# SCH_vibrating-mamba-snake_2024-07-07_1.net
KiCad netlist of a schematic drawn in EasyEDA
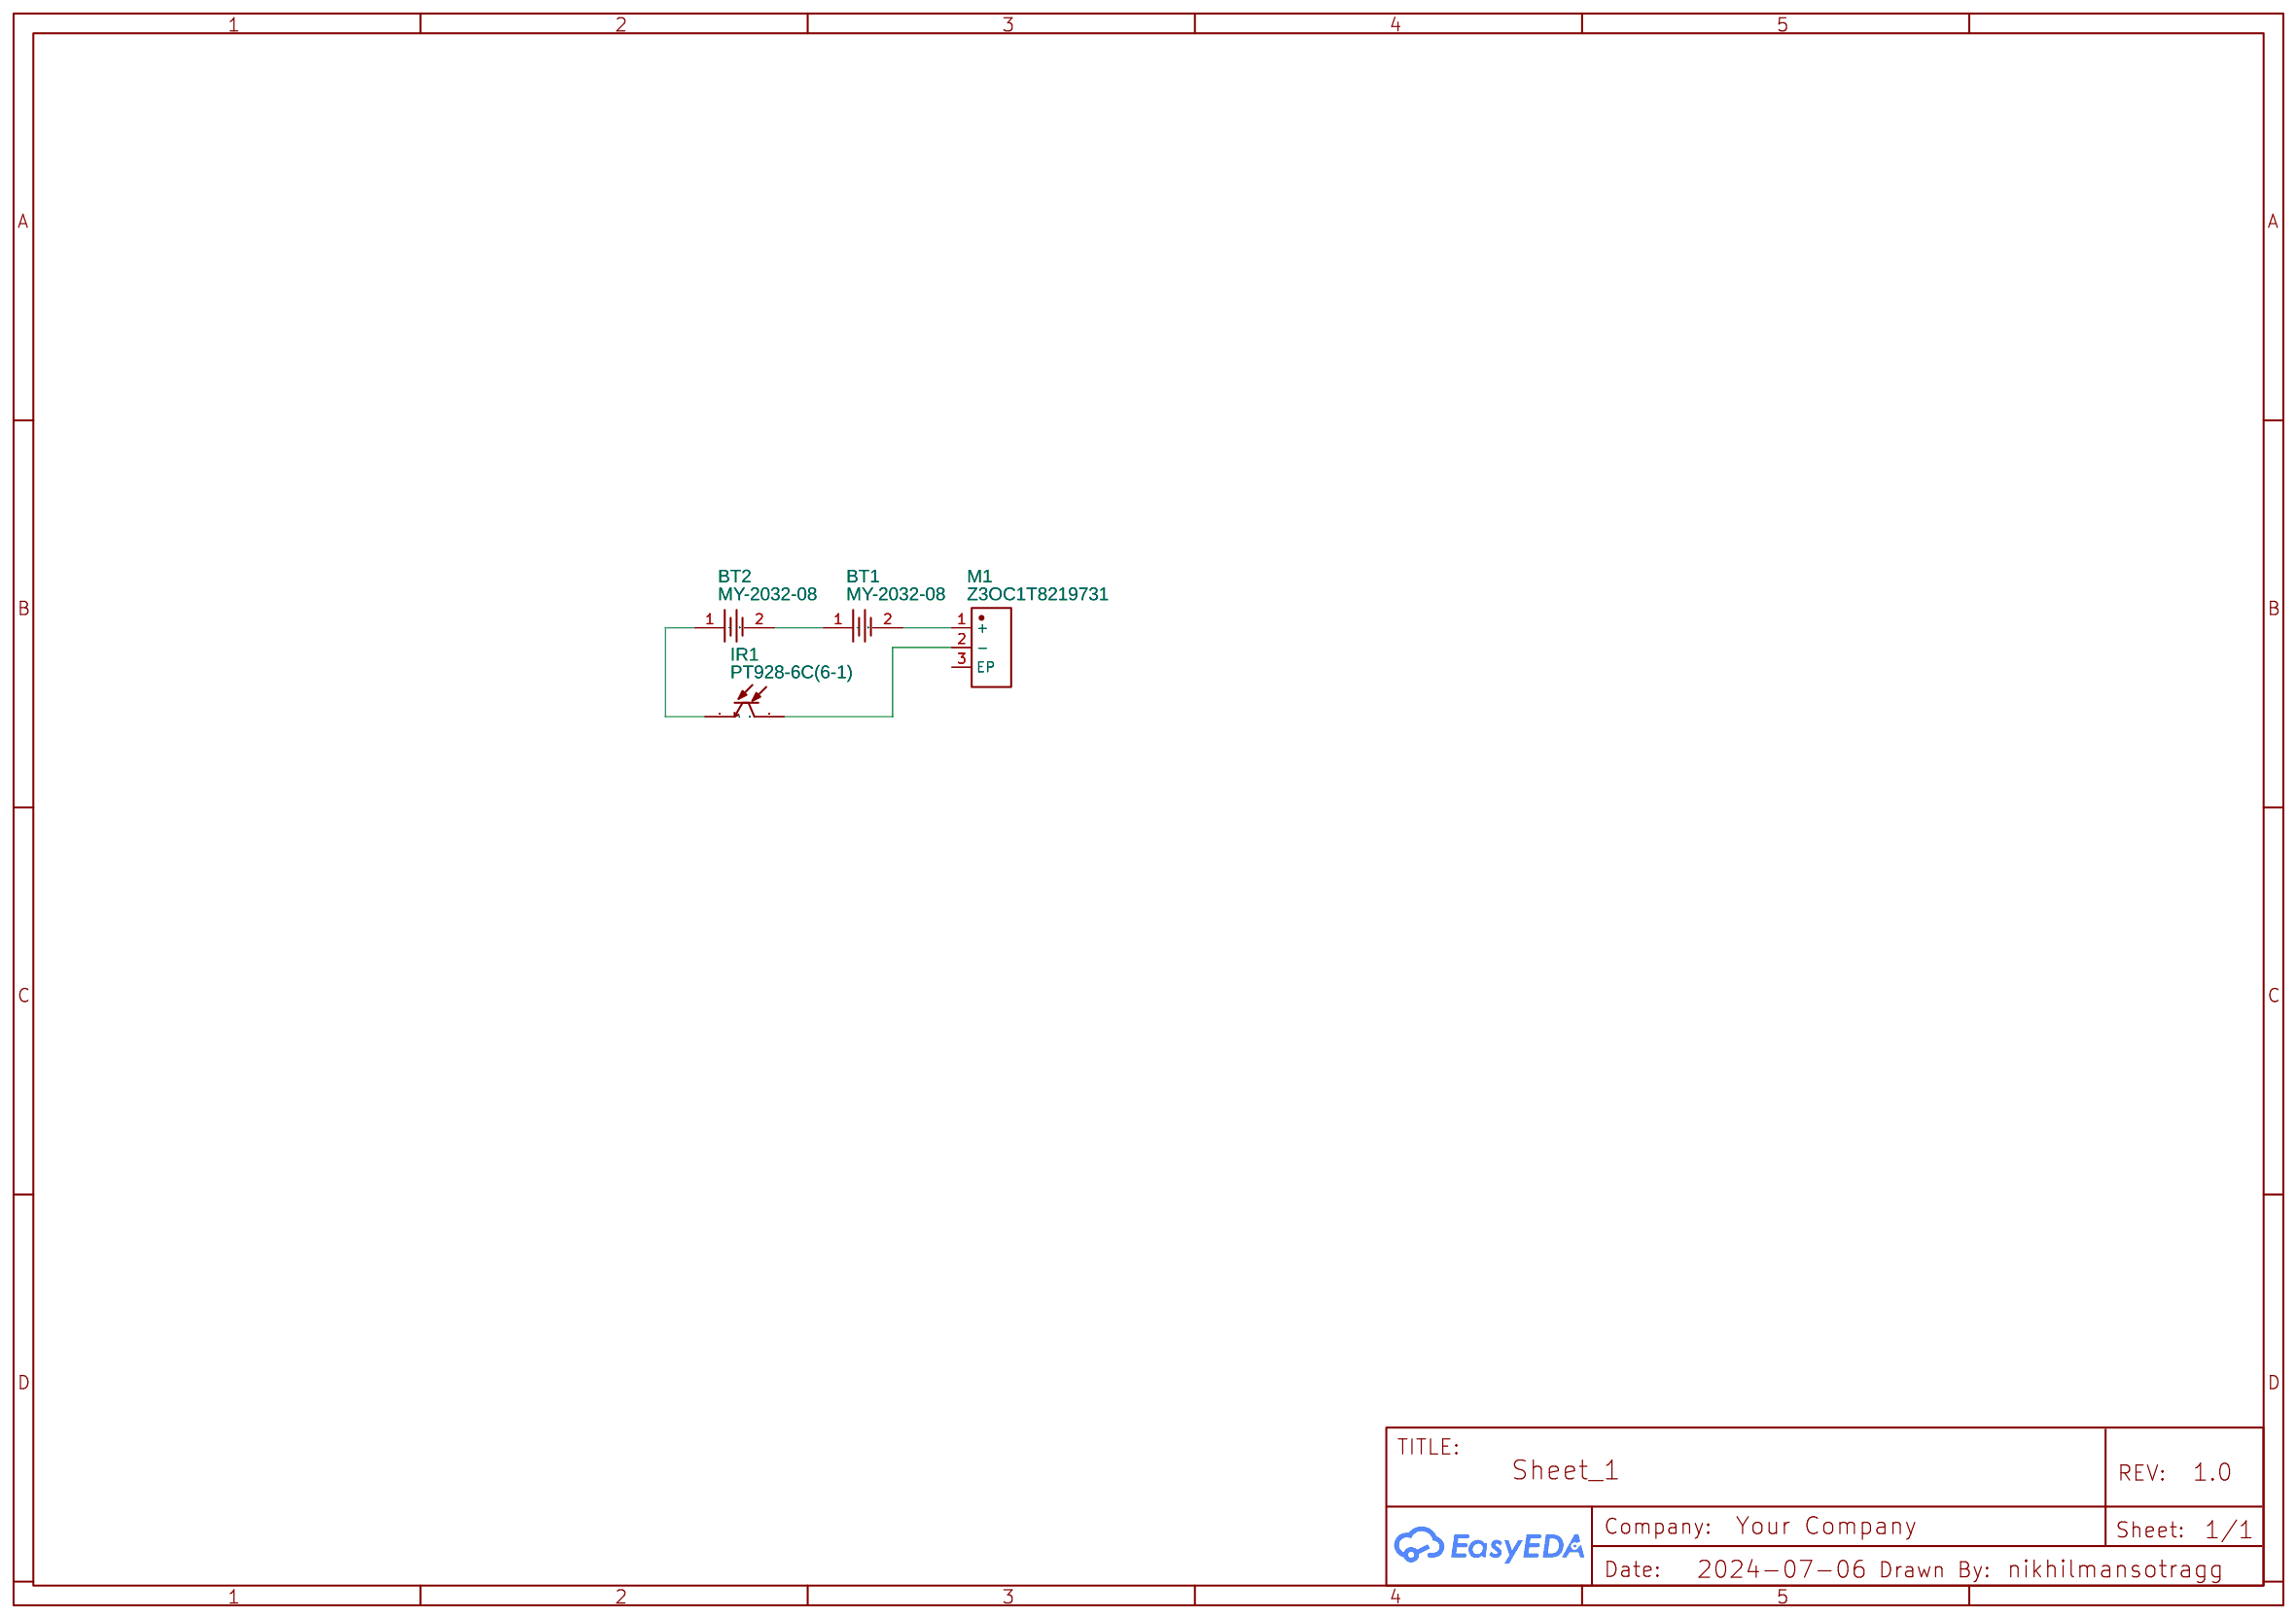
[diagram p0: schematic sheet]

(export (version "E")
  (design (tool "Eeschema 10.0.6"))
  (components
    (comp (ref "BT1")
      (value "MY-2032-08")
      (fields (field (name "Manufacturer") "MYOUNG(美阳)"))
      (libsource (lib "") (part "MY-2032-08"))
    )
    (comp (ref "BT2")
      (value "MY-2032-08")
      (fields (field (name "Manufacturer") "MYOUNG(美阳)"))
      (libsource (lib "") (part "MY-2032-08"))
    )
    (comp (ref "IR1")
      (value "PT928-6C(6-1)")
      (fields (field (name "Manufacturer") "EVERLIGHT(亿光)"))
      (libsource (lib "") (part "PT928-6C(6-1)"))
    )
    (comp (ref "M1")
      (value "Z3OC1T8219731")
      (fields (field (name "Manufacturer") "KOTL(金龙机电)"))
      (libsource (lib "") (part "Z3OC1T8219731"))
    )
  )
  (nets
    (net (code "1") (name "Net-(BT1-Pad1)") (class "Default")
      (node (ref "BT1") (pin "1") (pinfunction "1_1") (pintype "input"))
      (node (ref "BT2") (pin "2") (pinfunction "2_2") (pintype "input"))
    )
    (net (code "2") (name "Net-(IR1-C)") (class "Default")
      (node (ref "IR1") (pin "2") (pinfunction "C_2") (pintype "input"))
      (node (ref "M1") (pin "2") (pinfunction "-_2") (pintype "unspecified"))
    )
    (net (code "3") (name "Net-(IR1-E)") (class "Default")
      (node (ref "BT2") (pin "1") (pinfunction "1_1") (pintype "input"))
      (node (ref "IR1") (pin "1") (pinfunction "E_1") (pintype "input"))
    )
    (net (code "4") (name "Net-(M1-+)") (class "Default")
      (node (ref "BT1") (pin "2") (pinfunction "2_2") (pintype "input"))
      (node (ref "M1") (pin "1") (pinfunction "+_1") (pintype "unspecified"))
    )
    (net (code "5") (name "unconnected-(M1-EP-Pad3)") (class "Default")
      (node (ref "M1") (pin "3") (pinfunction "EP_3") (pintype "unspecified"))
    )
  )
)
